# MCP960XL-L0X-RL0X_EVM_v1_Eagle_7_x.net
KiCad netlist of a schematic drawn in EAGLE
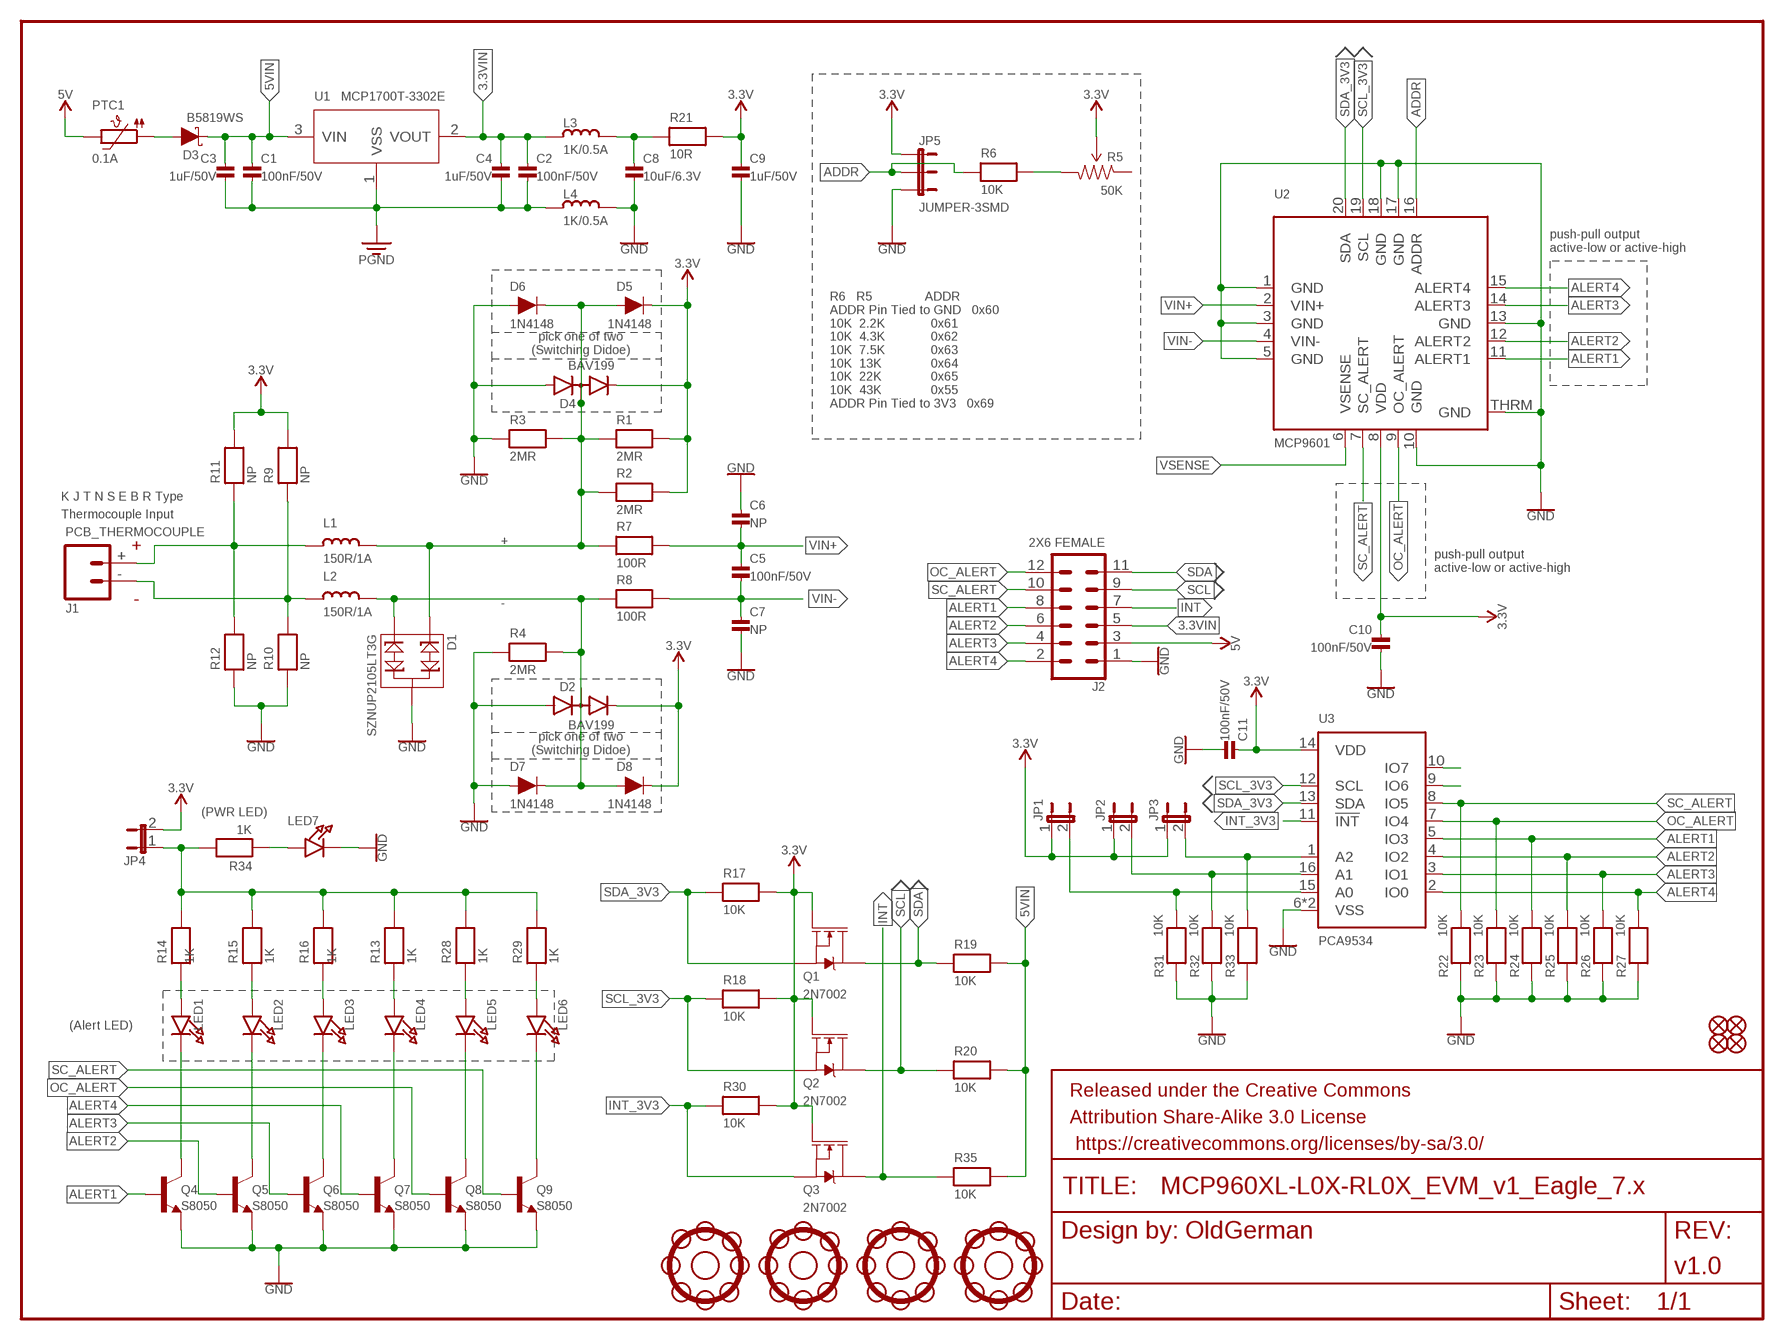
[diagram p0: schematic, sheet 1]

(export (version "E")
  (design (tool "Eeschema 10.0.6"))
  (components
    (comp (ref "C1")
      (value "100nF/50V")
      (footprint "eagle-import:0603")
      (libsource (lib "eagle-import") (part "CAP_CERAMIC0603"))
    )
    (comp (ref "C2")
      (value "100nF/50V")
      (footprint "eagle-import:0603")
      (libsource (lib "eagle-import") (part "CAP_CERAMIC0603"))
    )
    (comp (ref "C3")
      (value "1uF/50V")
      (footprint "eagle-import:0603")
      (libsource (lib "eagle-import") (part "CAP_CERAMIC0603"))
    )
    (comp (ref "C4")
      (value "1uF/50V")
      (footprint "eagle-import:0603")
      (libsource (lib "eagle-import") (part "CAP_CERAMIC0603"))
    )
    (comp (ref "C5")
      (value "100nF/50V")
      (footprint "eagle-import:0603")
      (libsource (lib "eagle-import") (part "CAP_CERAMIC0603"))
    )
    (comp (ref "C6")
      (value "NP")
      (footprint "eagle-import:0603")
      (libsource (lib "eagle-import") (part "CAP_CERAMIC0603"))
    )
    (comp (ref "C7")
      (value "NP")
      (footprint "eagle-import:0603")
      (libsource (lib "eagle-import") (part "CAP_CERAMIC0603"))
    )
    (comp (ref "C8")
      (value "10uF/6.3V")
      (footprint "eagle-import:0603")
      (libsource (lib "eagle-import") (part "CAP_CERAMIC0603"))
    )
    (comp (ref "C9")
      (value "1uF/50V")
      (footprint "eagle-import:0603")
      (libsource (lib "eagle-import") (part "CAP_CERAMIC0603"))
    )
    (comp (ref "C10")
      (value "100nF/50V")
      (footprint "eagle-import:0603")
      (libsource (lib "eagle-import") (part "CAP_CERAMIC0603"))
    )
    (comp (ref "C11")
      (value "100nF/50V")
      (footprint "eagle-import:0603")
      (libsource (lib "eagle-import") (part "CAP_CERAMIC0603"))
    )
    (comp (ref "D1")
      (value "SZNUP2105LT3G")
      (footprint "eagle-import:SOT23-3")
      (libsource (lib "eagle-import") (part "SZNUP2105LT3G"))
    )
    (comp (ref "D2")
      (value "BAV199")
      (footprint "eagle-import:SOT23-3")
      (libsource (lib "eagle-import") (part "BAV199"))
    )
    (comp (ref "D3")
      (value "B5819WS")
      (footprint "eagle-import:SOD-323")
      (libsource (lib "eagle-import") (part "DIODE_SCHOTTKYSOD323"))
    )
    (comp (ref "D4")
      (value "BAV199")
      (footprint "eagle-import:SOT23-3")
      (libsource (lib "eagle-import") (part "BAV199"))
    )
    (comp (ref "D5")
      (value "1N4148")
      (footprint "eagle-import:SOD-323")
      (libsource (lib "eagle-import") (part "DIODE"))
    )
    (comp (ref "D6")
      (value "1N4148")
      (footprint "eagle-import:SOD-323")
      (libsource (lib "eagle-import") (part "DIODE"))
    )
    (comp (ref "D7")
      (value "1N4148")
      (footprint "eagle-import:SOD-323")
      (libsource (lib "eagle-import") (part "DIODE"))
    )
    (comp (ref "D8")
      (value "1N4148")
      (footprint "eagle-import:SOD-323")
      (libsource (lib "eagle-import") (part "DIODE"))
    )
    (comp (ref "FID1")
      (value "FIDUCIAL1X2.5")
      (footprint "eagle-import:FIDUCIAL-1X2.5")
      (libsource (lib "eagle-import") (part "FIDUCIAL1X2.5"))
    )
    (comp (ref "FID2")
      (value "FIDUCIAL1X2.5")
      (footprint "eagle-import:FIDUCIAL-1X2.5")
      (libsource (lib "eagle-import") (part "FIDUCIAL1X2.5"))
    )
    (comp (ref "FID3")
      (value "FIDUCIAL1X2.5")
      (footprint "eagle-import:FIDUCIAL-1X2.5")
      (libsource (lib "eagle-import") (part "FIDUCIAL1X2.5"))
    )
    (comp (ref "FID4")
      (value "FIDUCIAL1X2.5")
      (footprint "eagle-import:FIDUCIAL-1X2.5")
      (libsource (lib "eagle-import") (part "FIDUCIAL1X2.5"))
    )
    (comp (ref "FRAME1")
      (value "FRAME-LETTER")
      (footprint "eagle-import:CREATIVE_COMMONS")
      (libsource (lib "eagle-import") (part "FRAME-LETTER"))
    )
    (comp (ref "J1")
      (value "PCB_THERMOCOUPLE")
      (footprint "eagle-import:PCC-SMP")
      (libsource (lib "eagle-import") (part "PCB_THERMOCOUPLE"))
    )
    (comp (ref "J2")
      (value "2X6 FEMALE")
      (footprint "eagle-import:2X6")
      (libsource (lib "eagle-import") (part "CONN_06X2PTH_FEMALE"))
    )
    (comp (ref "JP1")
      (value "JUMPER-2SMD-NC")
      (footprint "eagle-import:SJ_2S")
      (libsource (lib "eagle-import") (part "JUMPER-2SMD-NC"))
    )
    (comp (ref "JP2")
      (value "JUMPER-2SMD-NC")
      (footprint "eagle-import:SJ_2S")
      (libsource (lib "eagle-import") (part "JUMPER-2SMD-NC"))
    )
    (comp (ref "JP3")
      (value "JUMPER-2SMD-NC")
      (footprint "eagle-import:SJ_2S")
      (libsource (lib "eagle-import") (part "JUMPER-2SMD-NC"))
    )
    (comp (ref "JP4")
      (value "JUMPER-2SMD-NC")
      (footprint "eagle-import:SJ_2S")
      (libsource (lib "eagle-import") (part "JUMPER-2SMD-NC"))
    )
    (comp (ref "JP5")
      (value "JUMPER-3SMD")
      (footprint "eagle-import:SJ_3")
      (libsource (lib "eagle-import") (part "JUMPER-3SMD"))
    )
    (comp (ref "L1")
      (value "150R/1A")
      (footprint "eagle-import:0603")
      (libsource (lib "eagle-import") (part "INDUCTOR0603"))
    )
    (comp (ref "L2")
      (value "150R/1A")
      (footprint "eagle-import:0603")
      (libsource (lib "eagle-import") (part "INDUCTOR0603"))
    )
    (comp (ref "L3")
      (value "1K/0.5A")
      (footprint "eagle-import:0603")
      (libsource (lib "eagle-import") (part "INDUCTOR0603"))
    )
    (comp (ref "L4")
      (value "1K/0.5A")
      (footprint "eagle-import:0603")
      (libsource (lib "eagle-import") (part "INDUCTOR0603"))
    )
    (comp (ref "LED1")
      (value "LED0603")
      (footprint "eagle-import:CHIPLED_0603")
      (libsource (lib "eagle-import") (part "LED0603"))
    )
    (comp (ref "LED2")
      (value "LED0603")
      (footprint "eagle-import:CHIPLED_0603")
      (libsource (lib "eagle-import") (part "LED0603"))
    )
    (comp (ref "LED3")
      (value "LED0603")
      (footprint "eagle-import:CHIPLED_0603")
      (libsource (lib "eagle-import") (part "LED0603"))
    )
    (comp (ref "LED4")
      (value "LED0603")
      (footprint "eagle-import:CHIPLED_0603")
      (libsource (lib "eagle-import") (part "LED0603"))
    )
    (comp (ref "LED5")
      (value "LED0603")
      (footprint "eagle-import:CHIPLED_0603")
      (libsource (lib "eagle-import") (part "LED0603"))
    )
    (comp (ref "LED6")
      (value "LED0603")
      (footprint "eagle-import:CHIPLED_0603")
      (libsource (lib "eagle-import") (part "LED0603"))
    )
    (comp (ref "LED7")
      (value "LED0603")
      (footprint "eagle-import:CHIPLED_0603")
      (libsource (lib "eagle-import") (part "LED0603"))
    )
    (comp (ref "PTC1")
      (value "0.1A")
      (footprint "eagle-import:1206")
      (libsource (lib "eagle-import") (part "PTC1206"))
    )
    (comp (ref "Q1")
      (value "2N7002")
      (footprint "eagle-import:SOT23-3")
      (libsource (lib "eagle-import") (part "MOSFET-NCH-AO3404A"))
    )
    (comp (ref "Q2")
      (value "2N7002")
      (footprint "eagle-import:SOT23-3")
      (libsource (lib "eagle-import") (part "MOSFET-NCH-AO3404A"))
    )
    (comp (ref "Q3")
      (value "2N7002")
      (footprint "eagle-import:SOT23-3")
      (libsource (lib "eagle-import") (part "MOSFET-NCH-AO3404A"))
    )
    (comp (ref "Q4")
      (value "S8050")
      (footprint "eagle-import:SOT23-3")
      (libsource (lib "eagle-import") (part "TRANS_NPN-MMBT2222AL"))
    )
    (comp (ref "Q5")
      (value "S8050")
      (footprint "eagle-import:SOT23-3")
      (libsource (lib "eagle-import") (part "TRANS_NPN-MMBT2222AL"))
    )
    (comp (ref "Q6")
      (value "S8050")
      (footprint "eagle-import:SOT23-3")
      (libsource (lib "eagle-import") (part "TRANS_NPN-MMBT2222AL"))
    )
    (comp (ref "Q7")
      (value "S8050")
      (footprint "eagle-import:SOT23-3")
      (libsource (lib "eagle-import") (part "TRANS_NPN-MMBT2222AL"))
    )
    (comp (ref "Q8")
      (value "S8050")
      (footprint "eagle-import:SOT23-3")
      (libsource (lib "eagle-import") (part "TRANS_NPN-MMBT2222AL"))
    )
    (comp (ref "Q9")
      (value "S8050")
      (footprint "eagle-import:SOT23-3")
      (libsource (lib "eagle-import") (part "TRANS_NPN-MMBT2222AL"))
    )
    (comp (ref "R1")
      (value "2MR")
      (footprint "eagle-import:0603")
      (libsource (lib "eagle-import") (part "RESISTOR0603"))
    )
    (comp (ref "R2")
      (value "2MR")
      (footprint "eagle-import:0603")
      (libsource (lib "eagle-import") (part "RESISTOR0603"))
    )
    (comp (ref "R3")
      (value "2MR")
      (footprint "eagle-import:0603")
      (libsource (lib "eagle-import") (part "RESISTOR0603"))
    )
    (comp (ref "R4")
      (value "2MR")
      (footprint "eagle-import:0603")
      (libsource (lib "eagle-import") (part "RESISTOR0603"))
    )
    (comp (ref "R5")
      (value "50K")
      (footprint "eagle-import:TRIMPOT-3MM")
      (libsource (lib "eagle-import") (part "POT-SMD"))
    )
    (comp (ref "R6")
      (value "10K")
      (footprint "eagle-import:0603")
      (libsource (lib "eagle-import") (part "RESISTOR0603"))
    )
    (comp (ref "R7")
      (value "100R")
      (footprint "eagle-import:0603")
      (libsource (lib "eagle-import") (part "RESISTOR0603"))
    )
    (comp (ref "R8")
      (value "100R")
      (footprint "eagle-import:0603")
      (libsource (lib "eagle-import") (part "RESISTOR0603"))
    )
    (comp (ref "R9")
      (value "NP")
      (footprint "eagle-import:0603")
      (libsource (lib "eagle-import") (part "RESISTOR0603"))
    )
    (comp (ref "R10")
      (value "NP")
      (footprint "eagle-import:0603")
      (libsource (lib "eagle-import") (part "RESISTOR0603"))
    )
    (comp (ref "R11")
      (value "NP")
      (footprint "eagle-import:0603")
      (libsource (lib "eagle-import") (part "RESISTOR0603"))
    )
    (comp (ref "R12")
      (value "NP")
      (footprint "eagle-import:0603")
      (libsource (lib "eagle-import") (part "RESISTOR0603"))
    )
    (comp (ref "R13")
      (value "1K")
      (footprint "eagle-import:0603")
      (libsource (lib "eagle-import") (part "RESISTOR0603"))
    )
    (comp (ref "R14")
      (value "1K")
      (footprint "eagle-import:0603")
      (libsource (lib "eagle-import") (part "RESISTOR0603"))
    )
    (comp (ref "R15")
      (value "1K")
      (footprint "eagle-import:0603")
      (libsource (lib "eagle-import") (part "RESISTOR0603"))
    )
    (comp (ref "R16")
      (value "1K")
      (footprint "eagle-import:0603")
      (libsource (lib "eagle-import") (part "RESISTOR0603"))
    )
    (comp (ref "R17")
      (value "10K")
      (footprint "eagle-import:0603")
      (libsource (lib "eagle-import") (part "RESISTOR0603"))
    )
    (comp (ref "R18")
      (value "10K")
      (footprint "eagle-import:0603")
      (libsource (lib "eagle-import") (part "RESISTOR0603"))
    )
    (comp (ref "R19")
      (value "10K")
      (footprint "eagle-import:0603")
      (libsource (lib "eagle-import") (part "RESISTOR0603"))
    )
    (comp (ref "R20")
      (value "10K")
      (footprint "eagle-import:0603")
      (libsource (lib "eagle-import") (part "RESISTOR0603"))
    )
    (comp (ref "R21")
      (value "10R")
      (footprint "eagle-import:0603")
      (libsource (lib "eagle-import") (part "RESISTOR0603"))
    )
    (comp (ref "R22")
      (value "10K")
      (footprint "eagle-import:0603")
      (libsource (lib "eagle-import") (part "RESISTOR0603"))
    )
    (comp (ref "R23")
      (value "10K")
      (footprint "eagle-import:0603")
      (libsource (lib "eagle-import") (part "RESISTOR0603"))
    )
    (comp (ref "R24")
      (value "10K")
      (footprint "eagle-import:0603")
      (libsource (lib "eagle-import") (part "RESISTOR0603"))
    )
    (comp (ref "R25")
      (value "10K")
      (footprint "eagle-import:0603")
      (libsource (lib "eagle-import") (part "RESISTOR0603"))
    )
    (comp (ref "R26")
      (value "10K")
      (footprint "eagle-import:0603")
      (libsource (lib "eagle-import") (part "RESISTOR0603"))
    )
    (comp (ref "R27")
      (value "10K")
      (footprint "eagle-import:0603")
      (libsource (lib "eagle-import") (part "RESISTOR0603"))
    )
    (comp (ref "R28")
      (value "1K")
      (footprint "eagle-import:0603")
      (libsource (lib "eagle-import") (part "RESISTOR0603"))
    )
    (comp (ref "R29")
      (value "1K")
      (footprint "eagle-import:0603")
      (libsource (lib "eagle-import") (part "RESISTOR0603"))
    )
    (comp (ref "R30")
      (value "10K")
      (footprint "eagle-import:0603")
      (libsource (lib "eagle-import") (part "RESISTOR0603"))
    )
    (comp (ref "R31")
      (value "10K")
      (footprint "eagle-import:0603")
      (libsource (lib "eagle-import") (part "RESISTOR0603"))
    )
    (comp (ref "R32")
      (value "10K")
      (footprint "eagle-import:0603")
      (libsource (lib "eagle-import") (part "RESISTOR0603"))
    )
    (comp (ref "R33")
      (value "10K")
      (footprint "eagle-import:0603")
      (libsource (lib "eagle-import") (part "RESISTOR0603"))
    )
    (comp (ref "R34")
      (value "1K")
      (footprint "eagle-import:0603")
      (libsource (lib "eagle-import") (part "RESISTOR0603"))
    )
    (comp (ref "R35")
      (value "10K")
      (footprint "eagle-import:0603")
      (libsource (lib "eagle-import") (part "RESISTOR0603"))
    )
    (comp (ref "U$1")
      (value "SUN_HOLE_M3")
      (footprint "eagle-import:SUN_HOLE_M3")
      (libsource (lib "eagle-import") (part "SUN_HOLE_M3"))
    )
    (comp (ref "U$3")
      (value "SUN_HOLE_M3")
      (footprint "eagle-import:SUN_HOLE_M3")
      (libsource (lib "eagle-import") (part "SUN_HOLE_M3"))
    )
    (comp (ref "U$4")
      (value "SUN_HOLE_M3")
      (footprint "eagle-import:SUN_HOLE_M3")
      (libsource (lib "eagle-import") (part "SUN_HOLE_M3"))
    )
    (comp (ref "U$6")
      (value "SUN_HOLE_M3")
      (footprint "eagle-import:SUN_HOLE_M3")
      (libsource (lib "eagle-import") (part "SUN_HOLE_M3"))
    )
    (comp (ref "U1")
      (value "MCP1700T-3302E")
      (footprint "eagle-import:SOT23-3")
      (libsource (lib "eagle-import") (part "LDO_3PIN"))
    )
    (comp (ref "U2")
      (value "MCP9601")
      (footprint "eagle-import:VQFN20_5MM")
      (libsource (lib "eagle-import") (part "MCP9601"))
    )
    (comp (ref "U3")
      (value "PCA9534")
      (footprint "eagle-import:HVQFN16_4X4_0.65MM")
      (libsource (lib "eagle-import") (part "PCA9534"))
    )
  )
  (nets
    (net (code "1") (name "3.3V") (class "Default")
      (node (ref "C10") (pin "1") (pinfunction "P$1_1") (pintype "passive"))
      (node (ref "C11") (pin "1") (pinfunction "P$1_1") (pintype "passive"))
      (node (ref "C9") (pin "1") (pinfunction "P$1_1") (pintype "passive"))
      (node (ref "D2") (pin "3") (pinfunction "C_3") (pintype "passive"))
      (node (ref "D4") (pin "3") (pinfunction "C_3") (pintype "passive"))
      (node (ref "D5") (pin "C") (pinfunction "C_C") (pintype "passive"))
      (node (ref "D8") (pin "C") (pinfunction "C_C") (pintype "passive"))
      (node (ref "JP1") (pin "1") (pinfunction "1_1") (pintype "passive"))
      (node (ref "JP2") (pin "1") (pinfunction "1_1") (pintype "passive"))
      (node (ref "JP3") (pin "1") (pinfunction "1_1") (pintype "passive"))
      (node (ref "JP4") (pin "2") (pinfunction "2_2") (pintype "passive"))
      (node (ref "JP5") (pin "1") (pinfunction "1_1") (pintype "passive"))
      (node (ref "Q1") (pin "1") (pinfunction "G_1") (pintype "bidirectional"))
      (node (ref "Q2") (pin "1") (pinfunction "G_1") (pintype "bidirectional"))
      (node (ref "Q3") (pin "1") (pinfunction "G_1") (pintype "bidirectional"))
      (node (ref "R1") (pin "2") (pinfunction "2_2") (pintype "passive"))
      (node (ref "R11") (pin "2") (pinfunction "2_2") (pintype "passive"))
      (node (ref "R17") (pin "2") (pinfunction "2_2") (pintype "passive"))
      (node (ref "R18") (pin "2") (pinfunction "2_2") (pintype "passive"))
      (node (ref "R2") (pin "2") (pinfunction "2_2") (pintype "passive"))
      (node (ref "R21") (pin "2") (pinfunction "2_2") (pintype "passive"))
      (node (ref "R30") (pin "2") (pinfunction "2_2") (pintype "passive"))
      (node (ref "R5") (pin "2") (pinfunction "WIPER_2") (pintype "passive"))
      (node (ref "R9") (pin "2") (pinfunction "2_2") (pintype "passive"))
      (node (ref "U2") (pin "8") (pinfunction "VDD_8") (pintype "bidirectional"))
      (node (ref "U3") (pin "14") (pinfunction "VDD_14") (pintype "power_in"))
    )
    (net (code "2") (name "3.3VIN") (class "Default")
      (node (ref "C2") (pin "1") (pinfunction "P$1_1") (pintype "passive"))
      (node (ref "C4") (pin "1") (pinfunction "P$1_1") (pintype "passive"))
      (node (ref "J2") (pin "5") (pinfunction "5_5") (pintype "passive"))
      (node (ref "L3") (pin "1") (pinfunction "1_1") (pintype "passive"))
      (node (ref "U1") (pin "2") (pinfunction "VOUT_2") (pintype "bidirectional"))
    )
    (net (code "3") (name "5V") (class "Default")
      (node (ref "J2") (pin "3") (pinfunction "3_3") (pintype "passive"))
      (node (ref "PTC1") (pin "2") (pinfunction "2_2") (pintype "passive"))
    )
    (net (code "4") (name "5VIN") (class "Default")
      (node (ref "C1") (pin "1") (pinfunction "P$1_1") (pintype "passive"))
      (node (ref "C3") (pin "1") (pinfunction "P$1_1") (pintype "passive"))
      (node (ref "D3") (pin "C") (pinfunction "C_C") (pintype "passive"))
      (node (ref "R19") (pin "2") (pinfunction "2_2") (pintype "passive"))
      (node (ref "R20") (pin "2") (pinfunction "2_2") (pintype "passive"))
      (node (ref "R35") (pin "2") (pinfunction "2_2") (pintype "passive"))
      (node (ref "U1") (pin "3") (pinfunction "VIN_3") (pintype "bidirectional"))
    )
    (net (code "5") (name "ADDR") (class "Default")
      (node (ref "JP5") (pin "2") (pinfunction "2_2") (pintype "passive"))
      (node (ref "R6") (pin "1") (pinfunction "1_1") (pintype "passive"))
      (node (ref "U2") (pin "16") (pinfunction "ADDR_16") (pintype "bidirectional"))
    )
    (net (code "6") (name "ALERT1") (class "Default")
      (node (ref "J2") (pin "8") (pinfunction "8_8") (pintype "passive"))
      (node (ref "Q4") (pin "1") (pinfunction "B_1") (pintype "passive"))
      (node (ref "R24") (pin "2") (pinfunction "2_2") (pintype "passive"))
      (node (ref "U2") (pin "11") (pinfunction "ALERT1_11") (pintype "bidirectional"))
      (node (ref "U3") (pin "5") (pinfunction "IO3_5") (pintype "bidirectional"))
    )
    (net (code "7") (name "ALERT2") (class "Default")
      (node (ref "J2") (pin "6") (pinfunction "6_6") (pintype "passive"))
      (node (ref "Q5") (pin "1") (pinfunction "B_1") (pintype "passive"))
      (node (ref "R25") (pin "2") (pinfunction "2_2") (pintype "passive"))
      (node (ref "U2") (pin "12") (pinfunction "ALERT2_12") (pintype "bidirectional"))
      (node (ref "U3") (pin "4") (pinfunction "IO2_4") (pintype "bidirectional"))
    )
    (net (code "8") (name "ALERT3") (class "Default")
      (node (ref "J2") (pin "4") (pinfunction "4_4") (pintype "passive"))
      (node (ref "Q6") (pin "1") (pinfunction "B_1") (pintype "passive"))
      (node (ref "R26") (pin "2") (pinfunction "2_2") (pintype "passive"))
      (node (ref "U2") (pin "14") (pinfunction "ALERT3_14") (pintype "bidirectional"))
      (node (ref "U3") (pin "3") (pinfunction "IO1_3") (pintype "bidirectional"))
    )
    (net (code "9") (name "ALERT4") (class "Default")
      (node (ref "J2") (pin "2") (pinfunction "2_2") (pintype "passive"))
      (node (ref "Q7") (pin "1") (pinfunction "B_1") (pintype "passive"))
      (node (ref "R27") (pin "2") (pinfunction "2_2") (pintype "passive"))
      (node (ref "U2") (pin "15") (pinfunction "ALERT4_15") (pintype "bidirectional"))
      (node (ref "U3") (pin "2") (pinfunction "IO0_2") (pintype "bidirectional"))
    )
    (net (code "10") (name "GND") (class "Default")
      (node (ref "C10") (pin "2") (pinfunction "P$2_2") (pintype "passive"))
      (node (ref "C11") (pin "2") (pinfunction "P$2_2") (pintype "passive"))
      (node (ref "C6") (pin "1") (pinfunction "P$1_1") (pintype "passive"))
      (node (ref "C7") (pin "2") (pinfunction "P$2_2") (pintype "passive"))
      (node (ref "C8") (pin "2") (pinfunction "P$2_2") (pintype "passive"))
      (node (ref "C9") (pin "2") (pinfunction "P$2_2") (pintype "passive"))
      (node (ref "D1") (pin "3") (pinfunction "3_3") (pintype "bidirectional"))
      (node (ref "D2") (pin "1") (pinfunction "A_1") (pintype "passive"))
      (node (ref "D4") (pin "1") (pinfunction "A_1") (pintype "passive"))
      (node (ref "D6") (pin "A") (pinfunction "A_A") (pintype "passive"))
      (node (ref "D7") (pin "A") (pinfunction "A_A") (pintype "passive"))
      (node (ref "J2") (pin "1") (pinfunction "1_1") (pintype "passive"))
      (node (ref "JP5") (pin "3") (pinfunction "3_3") (pintype "passive"))
      (node (ref "L4") (pin "2") (pinfunction "2_2") (pintype "passive"))
      (node (ref "LED7") (pin "C") (pinfunction "C_C") (pintype "passive"))
      (node (ref "Q4") (pin "2") (pinfunction "E_2") (pintype "passive"))
      (node (ref "Q5") (pin "2") (pinfunction "E_2") (pintype "passive"))
      (node (ref "Q6") (pin "2") (pinfunction "E_2") (pintype "passive"))
      (node (ref "Q7") (pin "2") (pinfunction "E_2") (pintype "passive"))
      (node (ref "Q8") (pin "2") (pinfunction "E_2") (pintype "passive"))
      (node (ref "Q9") (pin "2") (pinfunction "E_2") (pintype "passive"))
      (node (ref "R10") (pin "1") (pinfunction "1_1") (pintype "passive"))
      (node (ref "R12") (pin "1") (pinfunction "1_1") (pintype "passive"))
      (node (ref "R22") (pin "1") (pinfunction "1_1") (pintype "passive"))
      (node (ref "R23") (pin "1") (pinfunction "1_1") (pintype "passive"))
      (node (ref "R24") (pin "1") (pinfunction "1_1") (pintype "passive"))
      (node (ref "R25") (pin "1") (pinfunction "1_1") (pintype "passive"))
      (node (ref "R26") (pin "1") (pinfunction "1_1") (pintype "passive"))
      (node (ref "R27") (pin "1") (pinfunction "1_1") (pintype "passive"))
      (node (ref "R3") (pin "1") (pinfunction "1_1") (pintype "passive"))
      (node (ref "R31") (pin "1") (pinfunction "1_1") (pintype "passive"))
      (node (ref "R32") (pin "1") (pinfunction "1_1") (pintype "passive"))
      (node (ref "R33") (pin "1") (pinfunction "1_1") (pintype "passive"))
      (node (ref "R4") (pin "1") (pinfunction "1_1") (pintype "passive"))
      (node (ref "U2") (pin "1") (pinfunction "GND_1") (pintype "bidirectional"))
      (node (ref "U2") (pin "10") (pinfunction "GND_10") (pintype "bidirectional"))
      (node (ref "U2") (pin "13") (pinfunction "GND_13") (pintype "bidirectional"))
      (node (ref "U2") (pin "17") (pinfunction "GND_17") (pintype "bidirectional"))
      (node (ref "U2") (pin "18") (pinfunction "GND_18") (pintype "bidirectional"))
      (node (ref "U2") (pin "3") (pinfunction "GND_3") (pintype "bidirectional"))
      (node (ref "U2") (pin "5") (pinfunction "GND_5") (pintype "bidirectional"))
      (node (ref "U2") (pin "THRM") (pinfunction "GND_THRM") (pintype "bidirectional"))
      (node (ref "U3") (pin "6") (pinfunction "VSS_6") (pintype "power_in"))
      (node (ref "U3") (pin "PAD") (pinfunction "VSS_PAD") (pintype "power_in"))
    )
    (net (code "11") (name "INT") (class "Default")
      (node (ref "J2") (pin "7") (pinfunction "7_7") (pintype "passive"))
      (node (ref "Q3") (pin "3") (pinfunction "D_3") (pintype "bidirectional"))
      (node (ref "R35") (pin "1") (pinfunction "1_1") (pintype "passive"))
    )
    (net (code "12") (name "INT_3V3") (class "Default")
      (node (ref "Q3") (pin "2") (pinfunction "S_2") (pintype "bidirectional"))
      (node (ref "R30") (pin "1") (pinfunction "1_1") (pintype "passive"))
      (node (ref "U3") (pin "11") (pinfunction "~{INT}_11") (pintype "open_collector"))
    )
    (net (code "13") (name "Net-(C8-P$1)") (class "Default")
      (node (ref "C8") (pin "1") (pinfunction "P$1_1") (pintype "passive"))
      (node (ref "L3") (pin "2") (pinfunction "2_2") (pintype "passive"))
      (node (ref "R21") (pin "1") (pinfunction "1_1") (pintype "passive"))
    )
    (net (code "14") (name "Net-(D2-AC)") (class "Default")
      (node (ref "D1") (pin "2") (pinfunction "2_2") (pintype "power_in"))
      (node (ref "D2") (pin "2") (pinfunction "AC_2") (pintype "passive"))
      (node (ref "D7") (pin "C") (pinfunction "C_C") (pintype "passive"))
      (node (ref "D8") (pin "A") (pinfunction "A_A") (pintype "passive"))
      (node (ref "L2") (pin "2") (pinfunction "2_2") (pintype "passive"))
      (node (ref "R4") (pin "2") (pinfunction "2_2") (pintype "passive"))
      (node (ref "R8") (pin "1") (pinfunction "1_1") (pintype "passive"))
    )
    (net (code "15") (name "Net-(D3-PadA)") (class "Default")
      (node (ref "D3") (pin "A") (pinfunction "A_A") (pintype "passive"))
      (node (ref "PTC1") (pin "1") (pinfunction "1_1") (pintype "passive"))
    )
    (net (code "16") (name "Net-(D4-AC)") (class "Default")
      (node (ref "D1") (pin "1") (pinfunction "1_1") (pintype "power_in"))
      (node (ref "D4") (pin "2") (pinfunction "AC_2") (pintype "passive"))
      (node (ref "D5") (pin "A") (pinfunction "A_A") (pintype "passive"))
      (node (ref "D6") (pin "C") (pinfunction "C_C") (pintype "passive"))
      (node (ref "L1") (pin "2") (pinfunction "2_2") (pintype "passive"))
      (node (ref "R1") (pin "1") (pinfunction "1_1") (pintype "passive"))
      (node (ref "R2") (pin "1") (pinfunction "1_1") (pintype "passive"))
      (node (ref "R3") (pin "2") (pinfunction "2_2") (pintype "passive"))
      (node (ref "R7") (pin "1") (pinfunction "1_1") (pintype "passive"))
    )
    (net (code "17") (name "Net-(J1-Pad+)") (class "Default")
      (node (ref "J1") (pin "+") (pinfunction "+_+") (pintype "passive"))
      (node (ref "L1") (pin "1") (pinfunction "1_1") (pintype "passive"))
      (node (ref "R11") (pin "1") (pinfunction "1_1") (pintype "passive"))
      (node (ref "R12") (pin "2") (pinfunction "2_2") (pintype "passive"))
    )
    (net (code "18") (name "Net-(J1-Pad-)") (class "Default")
      (node (ref "J1") (pin "-") (pinfunction "-_-") (pintype "passive"))
      (node (ref "L2") (pin "1") (pinfunction "1_1") (pintype "passive"))
      (node (ref "R10") (pin "2") (pinfunction "2_2") (pintype "passive"))
      (node (ref "R9") (pin "1") (pinfunction "1_1") (pintype "passive"))
    )
    (net (code "19") (name "Net-(JP4-Pad1)") (class "Default")
      (node (ref "JP4") (pin "1") (pinfunction "1_1") (pintype "passive"))
      (node (ref "R13") (pin "2") (pinfunction "2_2") (pintype "passive"))
      (node (ref "R14") (pin "2") (pinfunction "2_2") (pintype "passive"))
      (node (ref "R15") (pin "2") (pinfunction "2_2") (pintype "passive"))
      (node (ref "R16") (pin "2") (pinfunction "2_2") (pintype "passive"))
      (node (ref "R28") (pin "2") (pinfunction "2_2") (pintype "passive"))
      (node (ref "R29") (pin "2") (pinfunction "2_2") (pintype "passive"))
      (node (ref "R34") (pin "2") (pinfunction "2_2") (pintype "passive"))
    )
    (net (code "20") (name "Net-(LED1-PadA)") (class "Default")
      (node (ref "LED1") (pin "A") (pinfunction "A_A") (pintype "passive"))
      (node (ref "R14") (pin "1") (pinfunction "1_1") (pintype "passive"))
    )
    (net (code "21") (name "Net-(LED2-PadA)") (class "Default")
      (node (ref "LED2") (pin "A") (pinfunction "A_A") (pintype "passive"))
      (node (ref "R15") (pin "1") (pinfunction "1_1") (pintype "passive"))
    )
    (net (code "22") (name "Net-(LED3-PadA)") (class "Default")
      (node (ref "LED3") (pin "A") (pinfunction "A_A") (pintype "passive"))
      (node (ref "R16") (pin "1") (pinfunction "1_1") (pintype "passive"))
    )
    (net (code "23") (name "Net-(LED4-PadA)") (class "Default")
      (node (ref "LED4") (pin "A") (pinfunction "A_A") (pintype "passive"))
      (node (ref "R13") (pin "1") (pinfunction "1_1") (pintype "passive"))
    )
    (net (code "24") (name "Net-(LED5-PadA)") (class "Default")
      (node (ref "LED5") (pin "A") (pinfunction "A_A") (pintype "passive"))
      (node (ref "R28") (pin "1") (pinfunction "1_1") (pintype "passive"))
    )
    (net (code "25") (name "Net-(LED6-PadA)") (class "Default")
      (node (ref "LED6") (pin "A") (pinfunction "A_A") (pintype "passive"))
      (node (ref "R29") (pin "1") (pinfunction "1_1") (pintype "passive"))
    )
    (net (code "26") (name "Net-(LED7-PadA)") (class "Default")
      (node (ref "LED7") (pin "A") (pinfunction "A_A") (pintype "passive"))
      (node (ref "R34") (pin "1") (pinfunction "1_1") (pintype "passive"))
    )
    (net (code "27") (name "Net-(Q4-C)") (class "Default")
      (node (ref "LED1") (pin "C") (pinfunction "C_C") (pintype "passive"))
      (node (ref "Q4") (pin "3") (pinfunction "C_3") (pintype "passive"))
    )
    (net (code "28") (name "Net-(Q5-C)") (class "Default")
      (node (ref "LED2") (pin "C") (pinfunction "C_C") (pintype "passive"))
      (node (ref "Q5") (pin "3") (pinfunction "C_3") (pintype "passive"))
    )
    (net (code "29") (name "Net-(Q6-C)") (class "Default")
      (node (ref "LED3") (pin "C") (pinfunction "C_C") (pintype "passive"))
      (node (ref "Q6") (pin "3") (pinfunction "C_3") (pintype "passive"))
    )
    (net (code "30") (name "Net-(Q7-C)") (class "Default")
      (node (ref "LED4") (pin "C") (pinfunction "C_C") (pintype "passive"))
      (node (ref "Q7") (pin "3") (pinfunction "C_3") (pintype "passive"))
    )
    (net (code "31") (name "Net-(Q8-C)") (class "Default")
      (node (ref "LED5") (pin "C") (pinfunction "C_C") (pintype "passive"))
      (node (ref "Q8") (pin "3") (pinfunction "C_3") (pintype "passive"))
    )
    (net (code "32") (name "Net-(Q9-C)") (class "Default")
      (node (ref "LED6") (pin "C") (pinfunction "C_C") (pintype "passive"))
      (node (ref "Q9") (pin "3") (pinfunction "C_3") (pintype "passive"))
    )
    (net (code "33") (name "Net-(R5-CW)") (class "Default")
      (node (ref "R5") (pin "1") (pinfunction "CW_1") (pintype "passive"))
      (node (ref "R6") (pin "2") (pinfunction "2_2") (pintype "passive"))
    )
    (net (code "34") (name "Net-(U3-A0)") (class "Default")
      (node (ref "JP1") (pin "2") (pinfunction "2_2") (pintype "passive"))
      (node (ref "R31") (pin "2") (pinfunction "2_2") (pintype "passive"))
      (node (ref "U3") (pin "15") (pinfunction "A0_15") (pintype "input"))
    )
    (net (code "35") (name "Net-(U3-A1)") (class "Default")
      (node (ref "JP2") (pin "2") (pinfunction "2_2") (pintype "passive"))
      (node (ref "R32") (pin "2") (pinfunction "2_2") (pintype "passive"))
      (node (ref "U3") (pin "16") (pinfunction "A1_16") (pintype "input"))
    )
    (net (code "36") (name "Net-(U3-A2)") (class "Default")
      (node (ref "JP3") (pin "2") (pinfunction "2_2") (pintype "passive"))
      (node (ref "R33") (pin "2") (pinfunction "2_2") (pintype "passive"))
      (node (ref "U3") (pin "1") (pinfunction "A2_1") (pintype "input"))
    )
    (net (code "37") (name "OC_ALERT") (class "Default")
      (node (ref "J2") (pin "12") (pinfunction "12_12") (pintype "passive"))
      (node (ref "Q8") (pin "1") (pinfunction "B_1") (pintype "passive"))
      (node (ref "R23") (pin "2") (pinfunction "2_2") (pintype "passive"))
      (node (ref "U2") (pin "9") (pinfunction "OC_ALERT_9") (pintype "bidirectional"))
      (node (ref "U3") (pin "7") (pinfunction "IO4_7") (pintype "bidirectional"))
    )
    (net (code "38") (name "PGND") (class "Default")
      (node (ref "C1") (pin "2") (pinfunction "P$2_2") (pintype "passive"))
      (node (ref "C2") (pin "2") (pinfunction "P$2_2") (pintype "passive"))
      (node (ref "C3") (pin "2") (pinfunction "P$2_2") (pintype "passive"))
      (node (ref "C4") (pin "2") (pinfunction "P$2_2") (pintype "passive"))
      (node (ref "L4") (pin "1") (pinfunction "1_1") (pintype "passive"))
      (node (ref "U1") (pin "1") (pinfunction "VSS_1") (pintype "bidirectional"))
    )
    (net (code "39") (name "SCL") (class "Default")
      (node (ref "J2") (pin "9") (pinfunction "9_9") (pintype "passive"))
      (node (ref "Q2") (pin "3") (pinfunction "D_3") (pintype "bidirectional"))
      (node (ref "R20") (pin "1") (pinfunction "1_1") (pintype "passive"))
    )
    (net (code "40") (name "SCL_3V3") (class "Default")
      (node (ref "Q2") (pin "2") (pinfunction "S_2") (pintype "bidirectional"))
      (node (ref "R18") (pin "1") (pinfunction "1_1") (pintype "passive"))
      (node (ref "U2") (pin "19") (pinfunction "SCL_19") (pintype "bidirectional"))
      (node (ref "U3") (pin "12") (pinfunction "SCL_12") (pintype "input"))
    )
    (net (code "41") (name "SC_ALERT") (class "Default")
      (node (ref "J2") (pin "10") (pinfunction "10_10") (pintype "passive"))
      (node (ref "Q9") (pin "1") (pinfunction "B_1") (pintype "passive"))
      (node (ref "R22") (pin "2") (pinfunction "2_2") (pintype "passive"))
      (node (ref "U2") (pin "7") (pinfunction "SC_ALERT_7") (pintype "bidirectional"))
      (node (ref "U3") (pin "8") (pinfunction "IO5_8") (pintype "bidirectional"))
    )
    (net (code "42") (name "SDA") (class "Default")
      (node (ref "J2") (pin "11") (pinfunction "11_11") (pintype "passive"))
      (node (ref "Q1") (pin "3") (pinfunction "D_3") (pintype "bidirectional"))
      (node (ref "R19") (pin "1") (pinfunction "1_1") (pintype "passive"))
    )
    (net (code "43") (name "SDA_3V3") (class "Default")
      (node (ref "Q1") (pin "2") (pinfunction "S_2") (pintype "bidirectional"))
      (node (ref "R17") (pin "1") (pinfunction "1_1") (pintype "passive"))
      (node (ref "U2") (pin "20") (pinfunction "SDA_20") (pintype "bidirectional"))
      (node (ref "U3") (pin "13") (pinfunction "SDA_13") (pintype "bidirectional"))
    )
    (net (code "44") (name "VIN+") (class "Default")
      (node (ref "C5") (pin "1") (pinfunction "P$1_1") (pintype "passive"))
      (node (ref "C6") (pin "2") (pinfunction "P$2_2") (pintype "passive"))
      (node (ref "R7") (pin "2") (pinfunction "2_2") (pintype "passive"))
      (node (ref "U2") (pin "2") (pinfunction "VIN+_2") (pintype "bidirectional"))
    )
    (net (code "45") (name "VIN-") (class "Default")
      (node (ref "C5") (pin "2") (pinfunction "P$2_2") (pintype "passive"))
      (node (ref "C7") (pin "1") (pinfunction "P$1_1") (pintype "passive"))
      (node (ref "R8") (pin "2") (pinfunction "2_2") (pintype "passive"))
      (node (ref "U2") (pin "4") (pinfunction "VIN-_4") (pintype "bidirectional"))
    )
    (net (code "46") (name "VSENSE") (class "Default")
      (node (ref "U2") (pin "6") (pinfunction "VSENSE_6") (pintype "bidirectional"))
    )
    (net (code "47") (name "unconnected-(R5-CCW-Pad3)") (class "Default")
      (node (ref "R5") (pin "3") (pinfunction "CCW_3") (pintype "passive"))
    )
    (net (code "48") (name "unconnected-(U3-IO6-Pad9)") (class "Default")
      (node (ref "U3") (pin "9") (pinfunction "IO6_9") (pintype "bidirectional"))
    )
    (net (code "49") (name "unconnected-(U3-IO7-Pad10)") (class "Default")
      (node (ref "U3") (pin "10") (pinfunction "IO7_10") (pintype "bidirectional"))
    )
  )
)
